# UI-Computer.net
KiCad netlist of a schematic drawn in Altium Designer
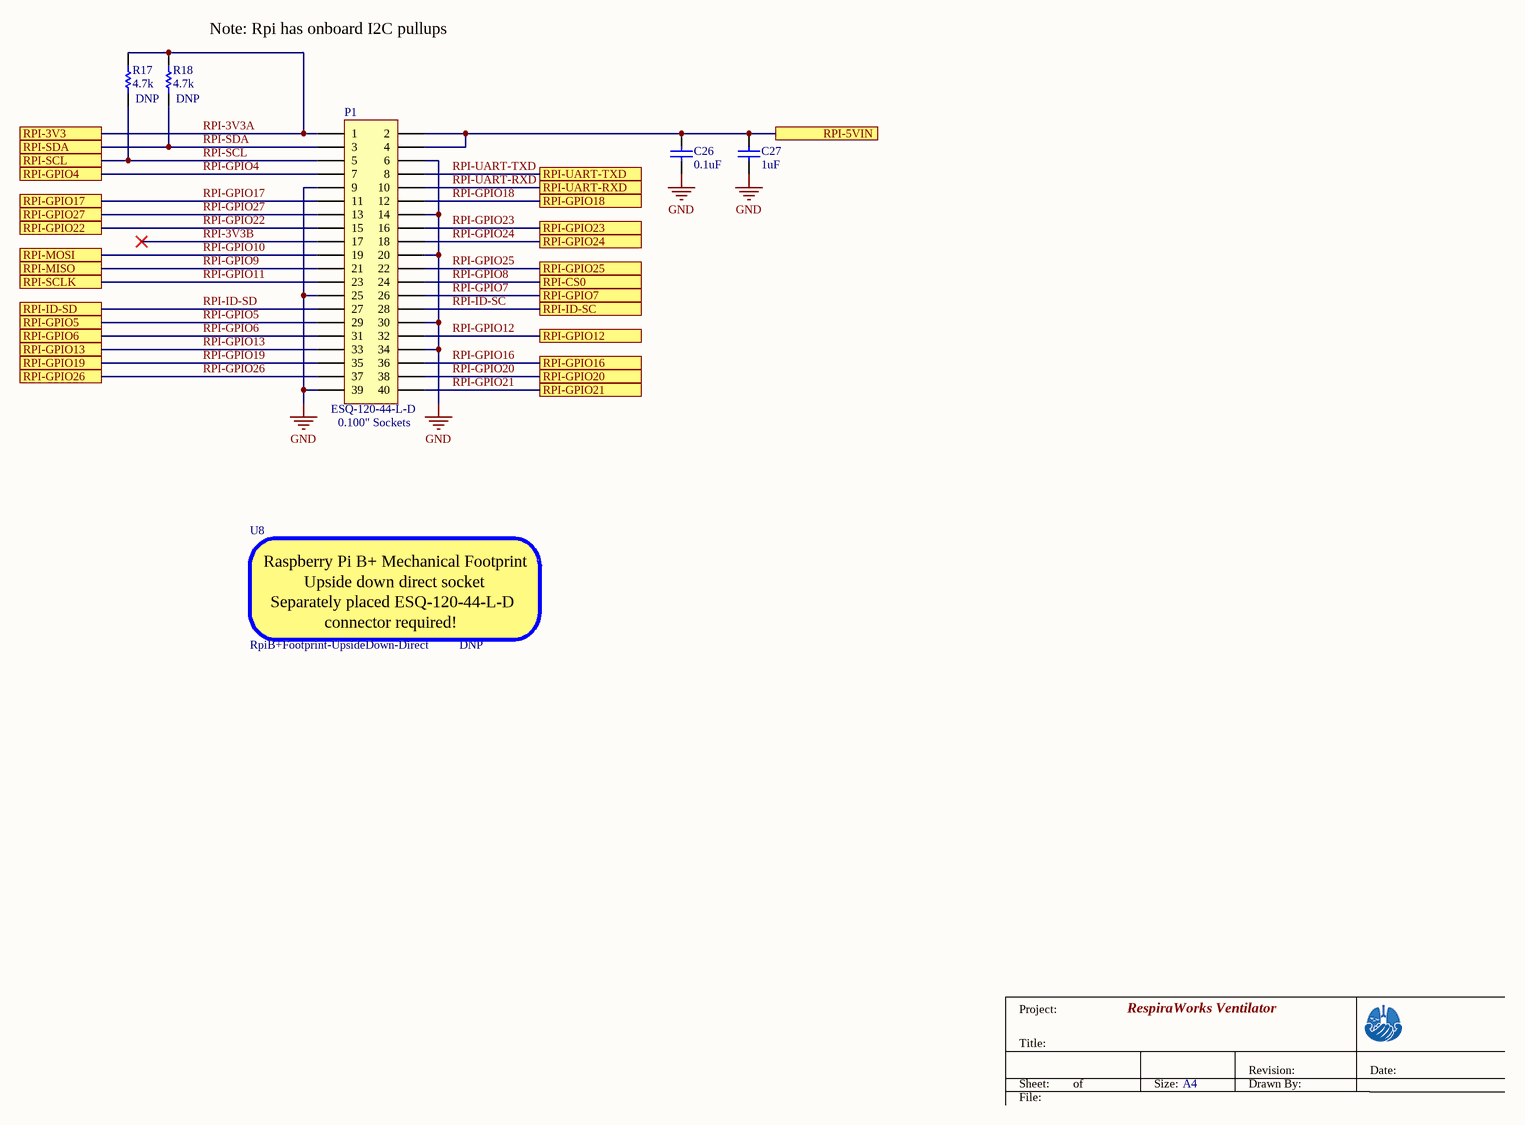
[diagram p0: UI-Computer.SchDoc]

(export (version "E")
  (design (tool "Eeschema 10.0.6"))
  (components
    (comp (ref "C26")
      (value "0.1uF")
      (footprint "CAP0603")
      (description "Cap 0603")
      (fields (field (name "MANUFACTURER") "Yageo") (field (name "VOLTAGE") "16V"))
      (libsource (lib "generic") (part "CAP 0603"))
    )
    (comp (ref "C27")
      (value "1uF")
      (footprint "CAP0603")
      (description "Cap 0603")
      (fields (field (name "MANUFACTURER") "Yageo") (field (name "VOLTAGE") "10V"))
      (libsource (lib "generic") (part "CAP 0603"))
    )
    (comp (ref "P1")
      (value "0.100\" Sockets")
      (footprint "ESQ-120-44-L-D")
      (description "Tall Female Header 0.100\" Pitch 20x2 Sockets")
      (fields (field (name "MANUFACTURER P/N") "ESQ-120-44-L-D") (field (name "MANUFACTURER") "Samtec"))
      (libsource (lib "samtec") (part "ESQ-120-44-L-D"))
    )
    (comp (ref "R17")
      (value "4.7k")
      (footprint "RES0603")
      (description "Res 0603")
      (fields
        (field (name "MANUFACTURER") "Yageo")
        (field (name "TOLERANCE") "1%")
        (field (name "DO NOT POPULATE") "DNP")
      )
      (libsource (lib "generic") (part "RES 0603"))
    )
    (comp (ref "R18")
      (value "4.7k")
      (footprint "RES0603")
      (description "Res 0603")
      (fields
        (field (name "MANUFACTURER") "Yageo")
        (field (name "TOLERANCE") "1%")
        (field (name "DO NOT POPULATE") "DNP")
      )
      (libsource (lib "generic") (part "RES 0603"))
    )
    (comp (ref "U8")
      (value "RpiB+Footprint-UpsideDown-Direct")
      (footprint "RpiB+UpsideDown-Direct")
      (description "Raspberry Pi B+ Footprint direct on PCB")
      (fields (field (name "DO NOT POPULATE") "DNP") (field (name "MANUFACTURER") "Raspberry Pi"))
      (libsource (lib "special") (part "RpiB+Footprint-UpsideDown-Direct"))
    )
  )
  (nets
    (net (code "1") (name "/RPI-3V3A") (class "Default")
      (node (ref "P1") (pin "1") (pinfunction "1_1") (pintype "passive"))
      (node (ref "R17") (pin "1") (pinfunction "1_1") (pintype "passive"))
      (node (ref "R18") (pin "1") (pinfunction "1_1") (pintype "passive"))
    )
    (net (code "2") (name "/RPI-3V3B") (class "Default")
      (node (ref "P1") (pin "17") (pinfunction "17_17") (pintype "passive+no_connect"))
    )
    (net (code "3") (name "/RPI-5VIN") (class "Default")
      (node (ref "C26") (pin "1") (pinfunction "1_1") (pintype "passive"))
      (node (ref "C27") (pin "1") (pinfunction "1_1") (pintype "passive"))
      (node (ref "P1") (pin "2") (pinfunction "2_2") (pintype "passive"))
      (node (ref "P1") (pin "4") (pinfunction "4_4") (pintype "passive"))
    )
    (net (code "4") (name "/RPI-GPIO4") (class "Default")
      (node (ref "P1") (pin "7") (pinfunction "7_7") (pintype "passive"))
    )
    (net (code "5") (name "/RPI-GPIO5") (class "Default")
      (node (ref "P1") (pin "29") (pinfunction "29_29") (pintype "passive"))
    )
    (net (code "6") (name "/RPI-GPIO6") (class "Default")
      (node (ref "P1") (pin "31") (pinfunction "31_31") (pintype "passive"))
    )
    (net (code "7") (name "/RPI-GPIO7") (class "Default")
      (node (ref "P1") (pin "26") (pinfunction "26_26") (pintype "passive"))
    )
    (net (code "8") (name "/RPI-GPIO8") (class "Default")
      (node (ref "P1") (pin "24") (pinfunction "24_24") (pintype "passive"))
    )
    (net (code "9") (name "/RPI-GPIO9") (class "Default")
      (node (ref "P1") (pin "21") (pinfunction "21_21") (pintype "passive"))
    )
    (net (code "10") (name "/RPI-GPIO10") (class "Default")
      (node (ref "P1") (pin "19") (pinfunction "19_19") (pintype "passive"))
    )
    (net (code "11") (name "/RPI-GPIO11") (class "Default")
      (node (ref "P1") (pin "23") (pinfunction "23_23") (pintype "passive"))
    )
    (net (code "12") (name "/RPI-GPIO12") (class "Default")
      (node (ref "P1") (pin "32") (pinfunction "32_32") (pintype "passive"))
    )
    (net (code "13") (name "/RPI-GPIO13") (class "Default")
      (node (ref "P1") (pin "33") (pinfunction "33_33") (pintype "passive"))
    )
    (net (code "14") (name "/RPI-GPIO16") (class "Default")
      (node (ref "P1") (pin "36") (pinfunction "36_36") (pintype "passive"))
    )
    (net (code "15") (name "/RPI-GPIO17") (class "Default")
      (node (ref "P1") (pin "11") (pinfunction "11_11") (pintype "passive"))
    )
    (net (code "16") (name "/RPI-GPIO18") (class "Default")
      (node (ref "P1") (pin "12") (pinfunction "12_12") (pintype "passive"))
    )
    (net (code "17") (name "/RPI-GPIO19") (class "Default")
      (node (ref "P1") (pin "35") (pinfunction "35_35") (pintype "passive"))
    )
    (net (code "18") (name "/RPI-GPIO20") (class "Default")
      (node (ref "P1") (pin "38") (pinfunction "38_38") (pintype "passive"))
    )
    (net (code "19") (name "/RPI-GPIO21") (class "Default")
      (node (ref "P1") (pin "40") (pinfunction "40_40") (pintype "passive"))
    )
    (net (code "20") (name "/RPI-GPIO22") (class "Default")
      (node (ref "P1") (pin "15") (pinfunction "15_15") (pintype "passive"))
    )
    (net (code "21") (name "/RPI-GPIO23") (class "Default")
      (node (ref "P1") (pin "16") (pinfunction "16_16") (pintype "passive"))
    )
    (net (code "22") (name "/RPI-GPIO24") (class "Default")
      (node (ref "P1") (pin "18") (pinfunction "18_18") (pintype "passive"))
    )
    (net (code "23") (name "/RPI-GPIO25") (class "Default")
      (node (ref "P1") (pin "22") (pinfunction "22_22") (pintype "passive"))
    )
    (net (code "24") (name "/RPI-GPIO26") (class "Default")
      (node (ref "P1") (pin "37") (pinfunction "37_37") (pintype "passive"))
    )
    (net (code "25") (name "/RPI-GPIO27") (class "Default")
      (node (ref "P1") (pin "13") (pinfunction "13_13") (pintype "passive"))
    )
    (net (code "26") (name "/RPI-ID-SC") (class "Default")
      (node (ref "P1") (pin "28") (pinfunction "28_28") (pintype "passive"))
    )
    (net (code "27") (name "/RPI-ID-SD") (class "Default")
      (node (ref "P1") (pin "27") (pinfunction "27_27") (pintype "passive"))
    )
    (net (code "28") (name "/RPI-SCL") (class "Default")
      (node (ref "P1") (pin "5") (pinfunction "5_5") (pintype "passive"))
      (node (ref "R17") (pin "2") (pinfunction "2_2") (pintype "passive"))
    )
    (net (code "29") (name "/RPI-SDA") (class "Default")
      (node (ref "P1") (pin "3") (pinfunction "3_3") (pintype "passive"))
      (node (ref "R18") (pin "2") (pinfunction "2_2") (pintype "passive"))
    )
    (net (code "30") (name "/RPI-UART-RXD") (class "Default")
      (node (ref "P1") (pin "10") (pinfunction "10_10") (pintype "passive"))
    )
    (net (code "31") (name "/RPI-UART-TXD") (class "Default")
      (node (ref "P1") (pin "8") (pinfunction "8_8") (pintype "passive"))
    )
    (net (code "32") (name "GND") (class "Default")
      (node (ref "C26") (pin "2") (pinfunction "2_2") (pintype "passive"))
      (node (ref "C27") (pin "2") (pinfunction "2_2") (pintype "passive"))
      (node (ref "P1") (pin "14") (pinfunction "14_14") (pintype "passive"))
      (node (ref "P1") (pin "20") (pinfunction "20_20") (pintype "passive"))
      (node (ref "P1") (pin "25") (pinfunction "25_25") (pintype "passive"))
      (node (ref "P1") (pin "30") (pinfunction "30_30") (pintype "passive"))
      (node (ref "P1") (pin "34") (pinfunction "34_34") (pintype "passive"))
      (node (ref "P1") (pin "39") (pinfunction "39_39") (pintype "passive"))
      (node (ref "P1") (pin "6") (pinfunction "6_6") (pintype "passive"))
      (node (ref "P1") (pin "9") (pinfunction "9_9") (pintype "passive"))
    )
  )
)
